# carcomputer_split1_top.net
KiCad netlist of a schematic drawn in EAGLE
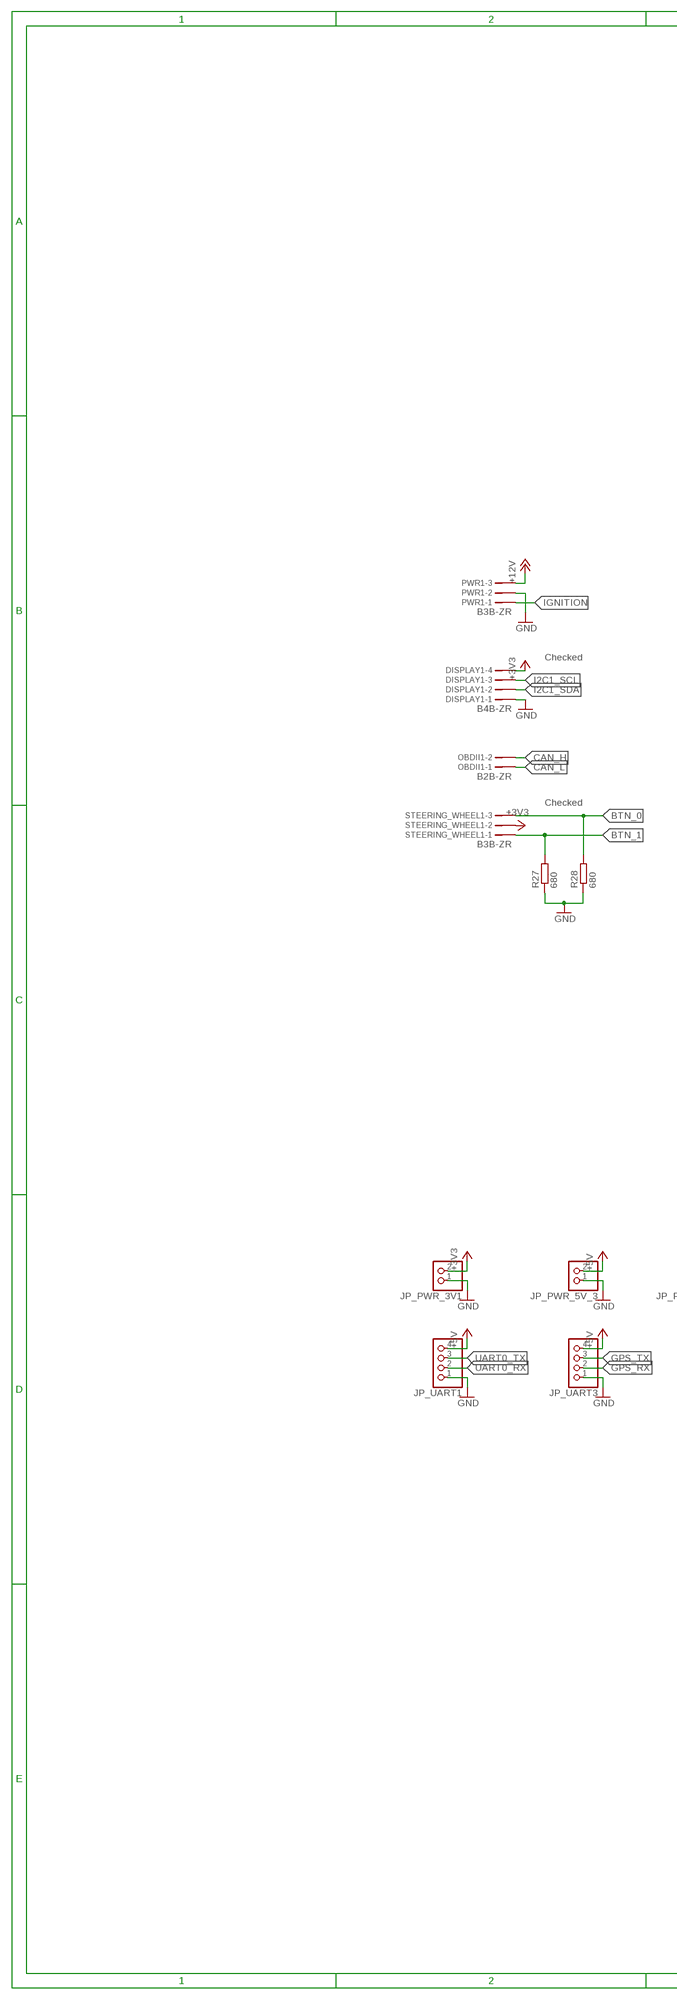
[diagram p0: schematic, sheet 1, part 1 of 2]
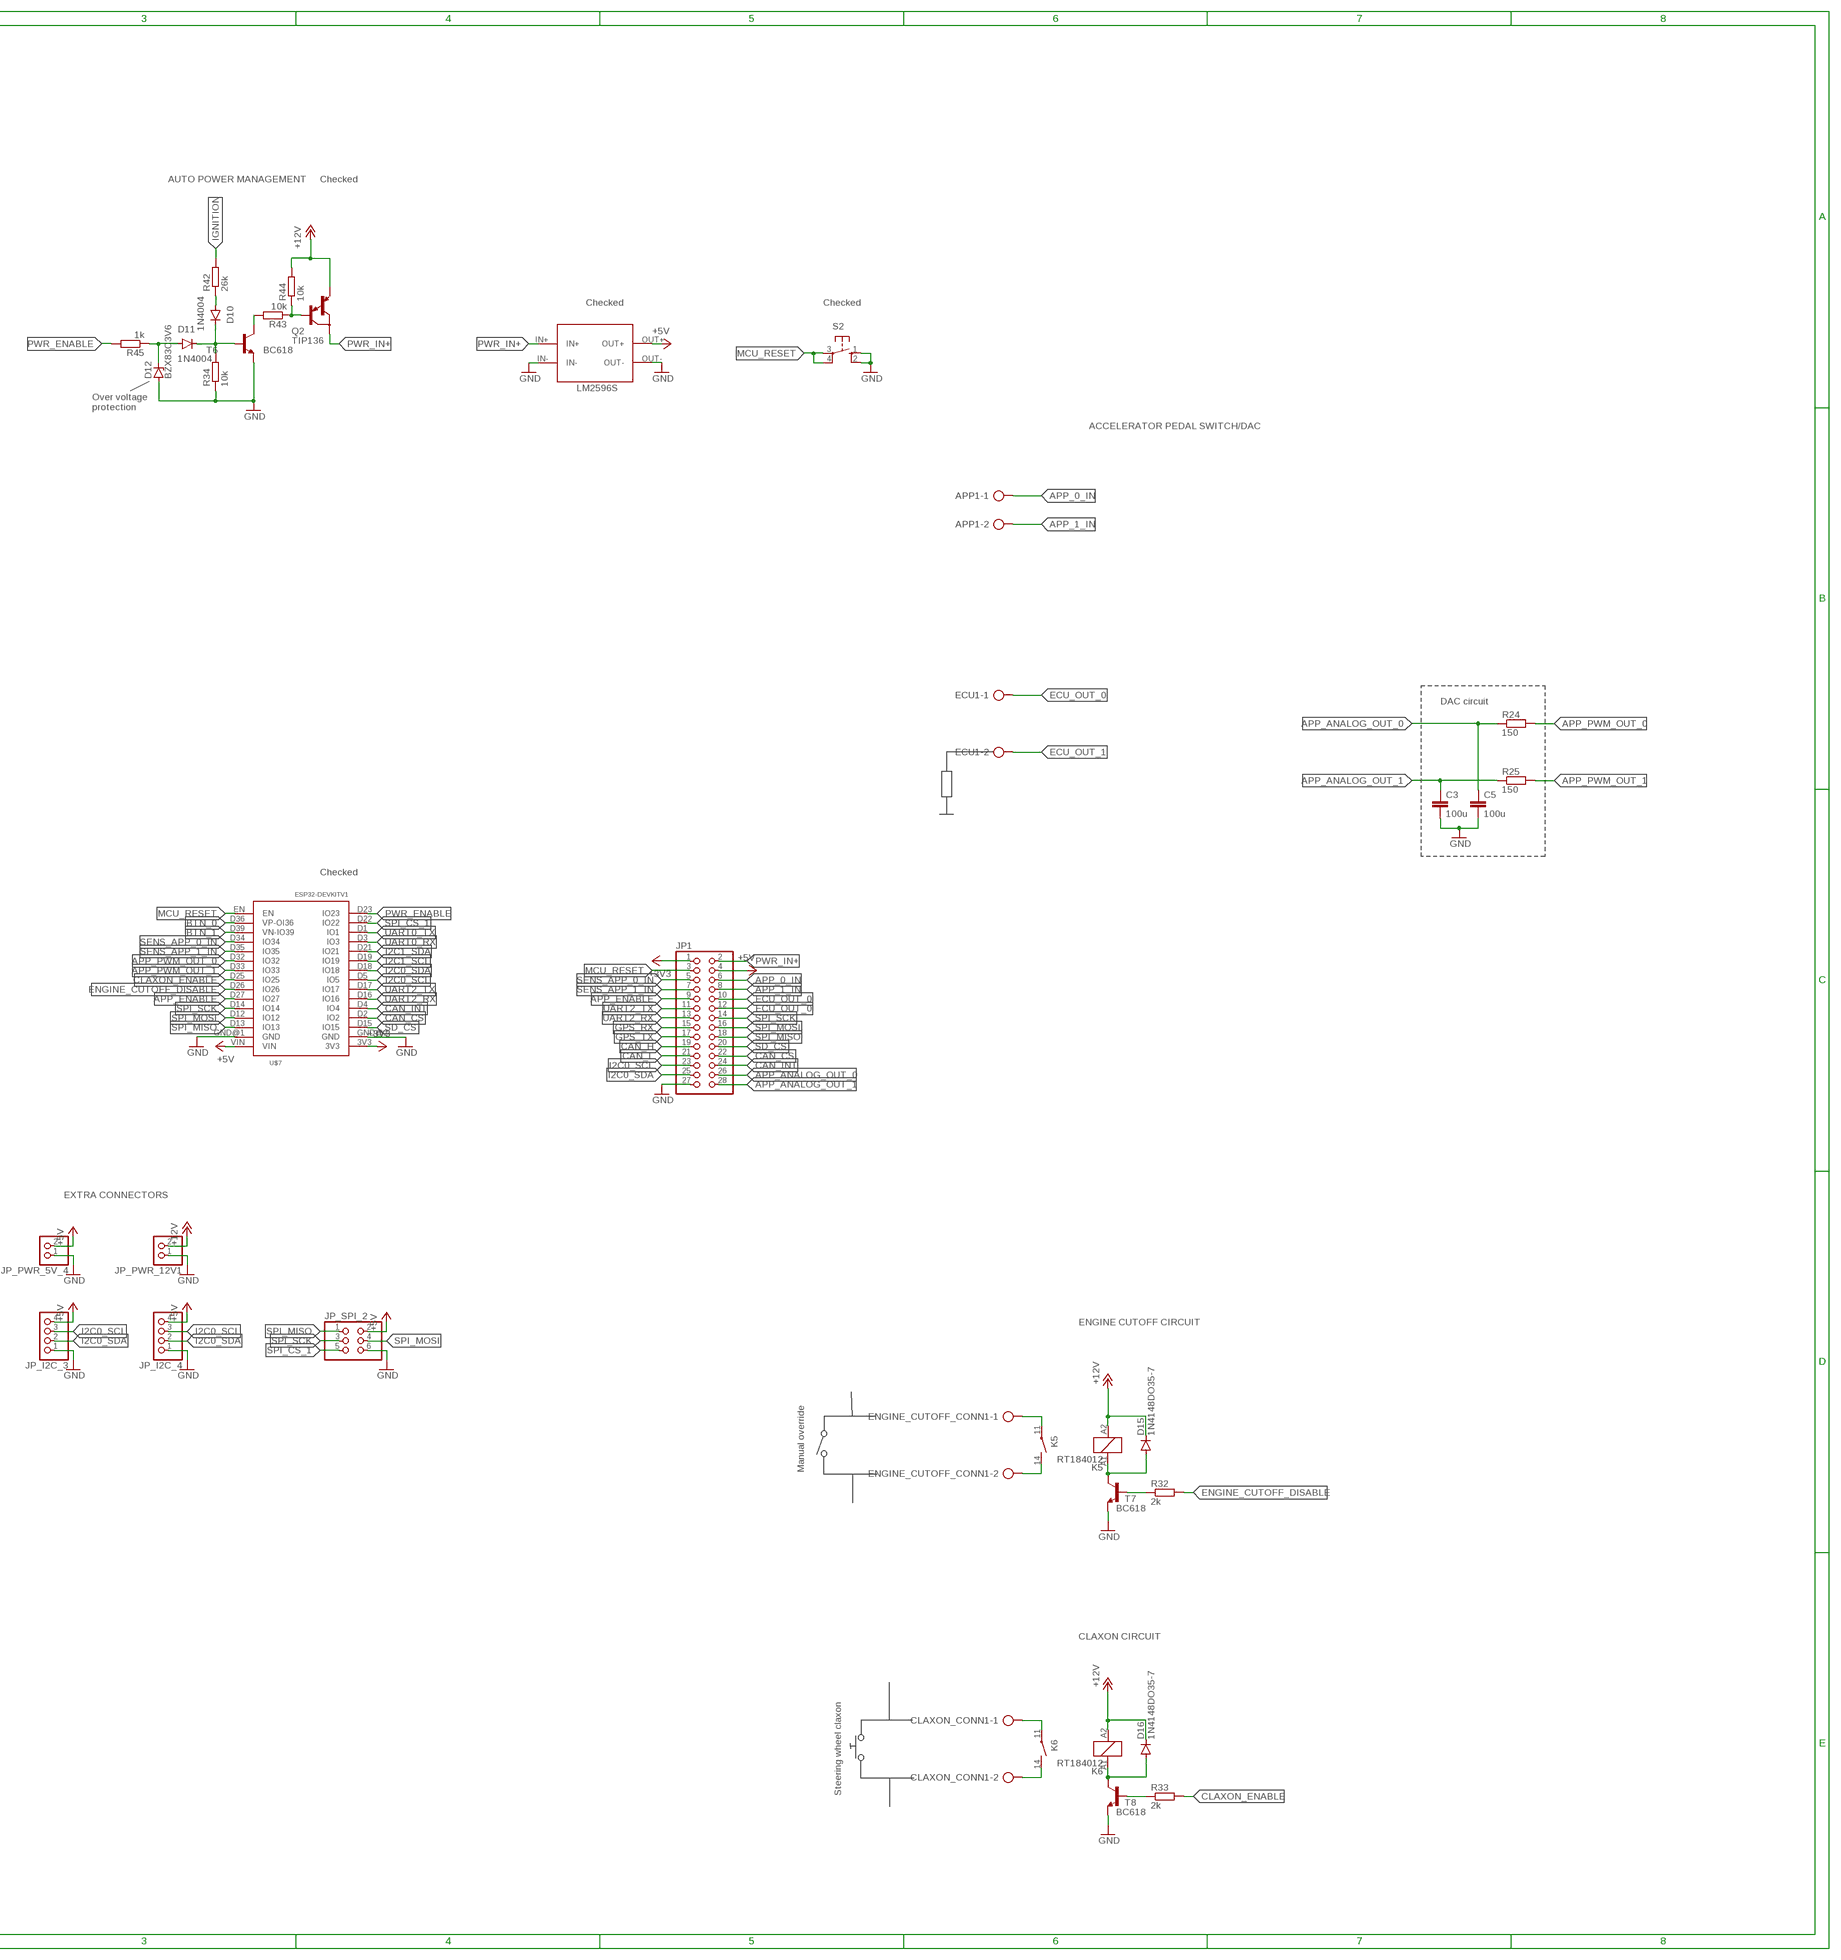
[diagram p1: schematic, sheet 1, part 2 of 2]

(export (version "E")
  (design (tool "Eeschema 10.0.6"))
  (components
    (comp (ref "APP1")
      (value "AK300/2")
      (footprint "eagle-import:AK300_2")
      (libsource (lib "eagle-import") (part "AK300/2"))
    )
    (comp (ref "C3")
      (value "100u")
      (footprint "eagle-import:C025-050X050")
      (libsource (lib "eagle-import") (part "C-EU025-050X050"))
    )
    (comp (ref "C5")
      (value "100u")
      (footprint "eagle-import:C025-050X050")
      (libsource (lib "eagle-import") (part "C-EU025-050X050"))
    )
    (comp (ref "CLAXON_CONN1")
      (value "AK300/2")
      (footprint "eagle-import:AK300_2")
      (libsource (lib "eagle-import") (part "AK300/2"))
    )
    (comp (ref "D10")
      (value "1N4004")
      (footprint "eagle-import:DO41-10")
      (libsource (lib "eagle-import") (part "1N4004"))
    )
    (comp (ref "D11")
      (value "1N4004")
      (footprint "eagle-import:DO41-10")
      (libsource (lib "eagle-import") (part "1N4004"))
    )
    (comp (ref "D12")
      (value "BZX83C3V6")
      (footprint "eagle-import:DO41Z10")
      (libsource (lib "eagle-import") (part "BZX85"))
    )
    (comp (ref "D15")
      (value "1N4148DO35-7")
      (footprint "eagle-import:DO35-7")
      (libsource (lib "eagle-import") (part "1N4148DO35-7"))
    )
    (comp (ref "D16")
      (value "1N4148DO35-7")
      (footprint "eagle-import:DO35-7")
      (libsource (lib "eagle-import") (part "1N4148DO35-7"))
    )
    (comp (ref "DISPLAY1")
      (value "B4B-ZR")
      (footprint "eagle-import:B4B-ZR")
      (fields (field (name "MF") "FARNELL") (field (name "MPN") "B4B-ZR(LF)(SN)"))
      (libsource (lib "eagle-import") (part "?4B-ZRB"))
    )
    (comp (ref "ECU1")
      (value "AK300/2")
      (footprint "eagle-import:AK300_2")
      (libsource (lib "eagle-import") (part "AK300/2"))
    )
    (comp (ref "ENGINE_CUTOFF_CONN1")
      (value "AK300/2")
      (footprint "eagle-import:AK300_2")
      (libsource (lib "eagle-import") (part "AK300/2"))
    )
    (comp (ref "JP1")
      (value "PINHD-2X14")
      (footprint "eagle-import:2X14")
      (libsource (lib "eagle-import") (part "PINHD-2X14"))
    )
    (comp (ref "JP_I2C_3")
      (value "PINHD-1X4")
      (footprint "eagle-import:1X04")
      (libsource (lib "eagle-import") (part "PINHD-1X4"))
    )
    (comp (ref "JP_I2C_4")
      (value "PINHD-1X4")
      (footprint "eagle-import:1X04")
      (libsource (lib "eagle-import") (part "PINHD-1X4"))
    )
    (comp (ref "JP_PWR_3V1")
      (value "PINHD-1X2")
      (footprint "eagle-import:1X02")
      (libsource (lib "eagle-import") (part "PINHD-1X2"))
    )
    (comp (ref "JP_PWR_5V_3")
      (value "PINHD-1X2")
      (footprint "eagle-import:1X02")
      (libsource (lib "eagle-import") (part "PINHD-1X2"))
    )
    (comp (ref "JP_PWR_5V_4")
      (value "PINHD-1X2")
      (footprint "eagle-import:1X02")
      (libsource (lib "eagle-import") (part "PINHD-1X2"))
    )
    (comp (ref "JP_PWR_12V1")
      (value "PINHD-1X2")
      (footprint "eagle-import:1X02")
      (libsource (lib "eagle-import") (part "PINHD-1X2"))
    )
    (comp (ref "JP_SPI_2")
      (value "PINHD-2X3")
      (footprint "eagle-import:2X03")
      (libsource (lib "eagle-import") (part "PINHD-2X3"))
    )
    (comp (ref "JP_UART1")
      (value "PINHD-1X4")
      (footprint "eagle-import:1X04")
      (libsource (lib "eagle-import") (part "PINHD-1X4"))
    )
    (comp (ref "JP_UART3")
      (value "PINHD-1X4")
      (footprint "eagle-import:1X04")
      (libsource (lib "eagle-import") (part "PINHD-1X4"))
    )
    (comp (ref "K5")
      (value "RT184012")
      (footprint "eagle-import:RT-N_O12A3.5")
      (fields (field (name "MF") "TYCO ELECTRONICS"))
      (libsource (lib "eagle-import") (part "RT?184012"))
    )
    (comp (ref "K6")
      (value "RT184012")
      (footprint "eagle-import:RT-N_O12A3.5")
      (fields (field (name "MF") "TYCO ELECTRONICS"))
      (libsource (lib "eagle-import") (part "RT?184012"))
    )
    (comp (ref "OBDII1")
      (value "B2B-ZR")
      (footprint "eagle-import:B2B-ZR")
      (libsource (lib "eagle-import") (part "?2B-ZRB"))
    )
    (comp (ref "PWR1")
      (value "B3B-ZR")
      (footprint "eagle-import:B3B-ZR")
      (libsource (lib "eagle-import") (part "?3B-ZRB"))
    )
    (comp (ref "Q2")
      (value "TIP136")
      (footprint "eagle-import:TO220")
      (libsource (lib "eagle-import") (part "TIP136"))
    )
    (comp (ref "R24")
      (value "150")
      (footprint "eagle-import:0207_7")
      (libsource (lib "eagle-import") (part "R-EU_0207/7"))
    )
    (comp (ref "R25")
      (value "150")
      (footprint "eagle-import:0207_7")
      (libsource (lib "eagle-import") (part "R-EU_0207/7"))
    )
    (comp (ref "R27")
      (value "680")
      (footprint "eagle-import:0207_7")
      (libsource (lib "eagle-import") (part "R-EU_0207/7"))
    )
    (comp (ref "R28")
      (value "680")
      (footprint "eagle-import:0207_7")
      (libsource (lib "eagle-import") (part "R-EU_0207/7"))
    )
    (comp (ref "R32")
      (value "2k")
      (footprint "eagle-import:0207_7")
      (libsource (lib "eagle-import") (part "R-EU_0207/7"))
    )
    (comp (ref "R33")
      (value "2k")
      (footprint "eagle-import:0207_7")
      (libsource (lib "eagle-import") (part "R-EU_0207/7"))
    )
    (comp (ref "R34")
      (value "10k")
      (footprint "eagle-import:0207_7")
      (libsource (lib "eagle-import") (part "R-EU_0207/7"))
    )
    (comp (ref "R42")
      (value "26k")
      (footprint "eagle-import:0207_7")
      (libsource (lib "eagle-import") (part "R-EU_0207/7"))
    )
    (comp (ref "R43")
      (value "10k")
      (footprint "eagle-import:0207_7")
      (libsource (lib "eagle-import") (part "R-EU_0207/7"))
    )
    (comp (ref "R44")
      (value "10k")
      (footprint "eagle-import:0207_7")
      (libsource (lib "eagle-import") (part "R-EU_0207/7"))
    )
    (comp (ref "R45")
      (value "1k")
      (footprint "eagle-import:0207_7")
      (libsource (lib "eagle-import") (part "R-EU_0207/7"))
    )
    (comp (ref "S2")
      (value "10-XX")
      (footprint "eagle-import:B3F-10XX")
      (fields (field (name "MPN") "B3F-1000"))
      (libsource (lib "eagle-import") (part "10-XX"))
    )
    (comp (ref "STEERING_WHEEL1")
      (value "B3B-ZR")
      (footprint "eagle-import:B3B-ZR")
      (libsource (lib "eagle-import") (part "?3B-ZRB"))
    )
    (comp (ref "T6")
      (value "BC618")
      (footprint "eagle-import:TO92-EBC")
      (libsource (lib "eagle-import") (part "BC618"))
    )
    (comp (ref "T7")
      (value "BC618")
      (footprint "eagle-import:TO92-EBC")
      (libsource (lib "eagle-import") (part "BC618"))
    )
    (comp (ref "T8")
      (value "BC618")
      (footprint "eagle-import:TO92-EBC")
      (libsource (lib "eagle-import") (part "BC618"))
    )
    (comp (ref "U$7")
      (value "ESP32DEVKITV1")
      (footprint "eagle-import:ESP32-DEVKITV1")
      (libsource (lib "eagle-import") (part "ESP32DEVKITV1"))
    )
    (comp (ref "U$10")
      (value "LM2596S")
      (footprint "eagle-import:LM2596S")
      (libsource (lib "eagle-import") (part "LM2596S"))
    )
  )
  (nets
    (net (code "1") (name "+3V3") (class "Default")
      (node (ref "DISPLAY1") (pin "4") (pinfunction "1_4") (pintype "passive"))
      (node (ref "JP1") (pin "1") (pinfunction "1_1") (pintype "passive"))
      (node (ref "JP_PWR_3V1") (pin "2") (pinfunction "2_2") (pintype "passive"))
      (node (ref "STEERING_WHEEL1") (pin "2") (pinfunction "1_2") (pintype "passive"))
      (node (ref "U$7") (pin "3V3") (pinfunction "3V3_3V3") (pintype "bidirectional"))
    )
    (net (code "2") (name "+5V") (class "Default")
      (node (ref "JP1") (pin "4") (pinfunction "4_4") (pintype "passive"))
      (node (ref "JP_I2C_3") (pin "4") (pinfunction "4_4") (pintype "passive"))
      (node (ref "JP_I2C_4") (pin "4") (pinfunction "4_4") (pintype "passive"))
      (node (ref "JP_PWR_5V_3") (pin "2") (pinfunction "2_2") (pintype "passive"))
      (node (ref "JP_PWR_5V_4") (pin "2") (pinfunction "2_2") (pintype "passive"))
      (node (ref "JP_SPI_2") (pin "2") (pinfunction "2_2") (pintype "passive"))
      (node (ref "JP_UART1") (pin "4") (pinfunction "4_4") (pintype "passive"))
      (node (ref "JP_UART3") (pin "4") (pinfunction "4_4") (pintype "passive"))
      (node (ref "U$10") (pin "OUT+") (pinfunction "OUT+_OUT+") (pintype "bidirectional"))
      (node (ref "U$7") (pin "VIN") (pinfunction "VIN_VIN") (pintype "bidirectional"))
    )
    (net (code "3") (name "+12V") (class "Default")
      (node (ref "D15") (pin "C") (pinfunction "C_C") (pintype "passive"))
      (node (ref "D16") (pin "C") (pinfunction "C_C") (pintype "passive"))
      (node (ref "JP_PWR_12V1") (pin "2") (pinfunction "2_2") (pintype "passive"))
      (node (ref "K5") (pin "A2") (pinfunction "2_A2") (pintype "passive"))
      (node (ref "K6") (pin "A2") (pinfunction "2_A2") (pintype "passive"))
      (node (ref "PWR1") (pin "3") (pinfunction "1_3") (pintype "passive"))
      (node (ref "Q2") (pin "3") (pinfunction "E_3") (pintype "passive"))
      (node (ref "R44") (pin "2") (pinfunction "2_2") (pintype "passive"))
    )
    (net (code "4") (name "APP_0_IN") (class "Default")
      (node (ref "APP1") (pin "1") (pinfunction "KL_1") (pintype "passive"))
      (node (ref "JP1") (pin "6") (pinfunction "6_6") (pintype "passive"))
    )
    (net (code "5") (name "APP_1_IN") (class "Default")
      (node (ref "APP1") (pin "2") (pinfunction "KL_2") (pintype "passive"))
      (node (ref "JP1") (pin "8") (pinfunction "8_8") (pintype "passive"))
    )
    (net (code "6") (name "APP_ANALOG_OUT_0") (class "Default")
      (node (ref "C5") (pin "1") (pinfunction "1_1") (pintype "passive"))
      (node (ref "JP1") (pin "26") (pinfunction "26_26") (pintype "passive"))
      (node (ref "R24") (pin "1") (pinfunction "1_1") (pintype "passive"))
    )
    (net (code "7") (name "APP_ANALOG_OUT_1") (class "Default")
      (node (ref "C3") (pin "1") (pinfunction "1_1") (pintype "passive"))
      (node (ref "JP1") (pin "28") (pinfunction "28_28") (pintype "passive"))
      (node (ref "R25") (pin "1") (pinfunction "1_1") (pintype "passive"))
    )
    (net (code "8") (name "APP_ENABLE") (class "Default")
      (node (ref "JP1") (pin "9") (pinfunction "9_9") (pintype "passive"))
      (node (ref "U$7") (pin "D27") (pinfunction "IO27_D27") (pintype "bidirectional"))
    )
    (net (code "9") (name "APP_PWM_OUT_0") (class "Default")
      (node (ref "R24") (pin "2") (pinfunction "2_2") (pintype "passive"))
      (node (ref "U$7") (pin "D32") (pinfunction "IO32_D32") (pintype "bidirectional"))
    )
    (net (code "10") (name "APP_PWM_OUT_1") (class "Default")
      (node (ref "R25") (pin "2") (pinfunction "2_2") (pintype "passive"))
      (node (ref "U$7") (pin "D33") (pinfunction "IO33_D33") (pintype "bidirectional"))
    )
    (net (code "11") (name "BTN_0") (class "Default")
      (node (ref "R28") (pin "2") (pinfunction "2_2") (pintype "passive"))
      (node (ref "STEERING_WHEEL1") (pin "3") (pinfunction "1_3") (pintype "passive"))
      (node (ref "U$7") (pin "D36") (pinfunction "VP-OI36_D36") (pintype "bidirectional"))
    )
    (net (code "12") (name "BTN_1") (class "Default")
      (node (ref "R27") (pin "2") (pinfunction "2_2") (pintype "passive"))
      (node (ref "STEERING_WHEEL1") (pin "1") (pinfunction "1_1") (pintype "passive"))
      (node (ref "U$7") (pin "D39") (pinfunction "VN-IO39_D39") (pintype "bidirectional"))
    )
    (net (code "13") (name "CAN_CS") (class "Default")
      (node (ref "JP1") (pin "22") (pinfunction "22_22") (pintype "passive"))
      (node (ref "U$7") (pin "D2") (pinfunction "IO2_D2") (pintype "bidirectional"))
    )
    (net (code "14") (name "CAN_H") (class "Default")
      (node (ref "JP1") (pin "19") (pinfunction "19_19") (pintype "passive"))
      (node (ref "OBDII1") (pin "2") (pinfunction "1_2") (pintype "passive"))
    )
    (net (code "15") (name "CAN_INT") (class "Default")
      (node (ref "JP1") (pin "24") (pinfunction "24_24") (pintype "passive"))
      (node (ref "U$7") (pin "D4") (pinfunction "IO4_D4") (pintype "bidirectional"))
    )
    (net (code "16") (name "CAN_L") (class "Default")
      (node (ref "JP1") (pin "21") (pinfunction "21_21") (pintype "passive"))
      (node (ref "OBDII1") (pin "1") (pinfunction "1_1") (pintype "passive"))
    )
    (net (code "17") (name "CLAXON_ENABLE") (class "Default")
      (node (ref "R33") (pin "2") (pinfunction "2_2") (pintype "passive"))
      (node (ref "U$7") (pin "D25") (pinfunction "IO25_D25") (pintype "bidirectional"))
    )
    (net (code "18") (name "ECU_OUT_0") (class "Default")
      (node (ref "ECU1") (pin "1") (pinfunction "KL_1") (pintype "passive"))
      (node (ref "JP1") (pin "10") (pinfunction "10_10") (pintype "passive"))
      (node (ref "JP1") (pin "12") (pinfunction "12_12") (pintype "passive"))
    )
    (net (code "19") (name "ECU_OUT_1") (class "Default")
      (node (ref "ECU1") (pin "2") (pinfunction "KL_2") (pintype "passive"))
    )
    (net (code "20") (name "ENGINE_CUTOFF_DISABLE") (class "Default")
      (node (ref "R32") (pin "2") (pinfunction "2_2") (pintype "passive"))
      (node (ref "U$7") (pin "D26") (pinfunction "IO26_D26") (pintype "bidirectional"))
    )
    (net (code "21") (name "GND") (class "Default")
      (node (ref "C3") (pin "2") (pinfunction "2_2") (pintype "passive"))
      (node (ref "C5") (pin "2") (pinfunction "2_2") (pintype "passive"))
      (node (ref "D12") (pin "A") (pinfunction "A_A") (pintype "passive"))
      (node (ref "DISPLAY1") (pin "1") (pinfunction "1_1") (pintype "passive"))
      (node (ref "JP1") (pin "27") (pinfunction "27_27") (pintype "passive"))
      (node (ref "JP_I2C_3") (pin "1") (pinfunction "1_1") (pintype "passive"))
      (node (ref "JP_I2C_4") (pin "1") (pinfunction "1_1") (pintype "passive"))
      (node (ref "JP_PWR_12V1") (pin "1") (pinfunction "1_1") (pintype "passive"))
      (node (ref "JP_PWR_3V1") (pin "1") (pinfunction "1_1") (pintype "passive"))
      (node (ref "JP_PWR_5V_3") (pin "1") (pinfunction "1_1") (pintype "passive"))
      (node (ref "JP_PWR_5V_4") (pin "1") (pinfunction "1_1") (pintype "passive"))
      (node (ref "JP_SPI_2") (pin "6") (pinfunction "6_6") (pintype "passive"))
      (node (ref "JP_UART1") (pin "1") (pinfunction "1_1") (pintype "passive"))
      (node (ref "JP_UART3") (pin "1") (pinfunction "1_1") (pintype "passive"))
      (node (ref "PWR1") (pin "2") (pinfunction "1_2") (pintype "passive"))
      (node (ref "R27") (pin "1") (pinfunction "1_1") (pintype "passive"))
      (node (ref "R28") (pin "1") (pinfunction "1_1") (pintype "passive"))
      (node (ref "R34") (pin "1") (pinfunction "1_1") (pintype "passive"))
      (node (ref "S2") (pin "1") (pinfunction "S_1") (pintype "passive"))
      (node (ref "S2") (pin "2") (pinfunction "S1_2") (pintype "passive"))
      (node (ref "T6") (pin "E") (pinfunction "E_E") (pintype "passive"))
      (node (ref "T7") (pin "E") (pinfunction "E_E") (pintype "passive"))
      (node (ref "T8") (pin "E") (pinfunction "E_E") (pintype "passive"))
      (node (ref "U$10") (pin "IN-") (pinfunction "IN-_IN-") (pintype "bidirectional"))
      (node (ref "U$10") (pin "OUT-") (pinfunction "OUT-_OUT-") (pintype "bidirectional"))
      (node (ref "U$7") (pin "GND@1") (pinfunction "GND_GND@1") (pintype "bidirectional"))
      (node (ref "U$7") (pin "GND@2") (pinfunction "GND_GND@2") (pintype "bidirectional"))
    )
    (net (code "22") (name "GPS_RX") (class "Default")
      (node (ref "JP1") (pin "15") (pinfunction "15_15") (pintype "passive"))
      (node (ref "JP_UART3") (pin "2") (pinfunction "2_2") (pintype "passive"))
    )
    (net (code "23") (name "GPS_TX") (class "Default")
      (node (ref "JP1") (pin "17") (pinfunction "17_17") (pintype "passive"))
      (node (ref "JP_UART3") (pin "3") (pinfunction "3_3") (pintype "passive"))
    )
    (net (code "24") (name "I2C0_SCL") (class "Default")
      (node (ref "JP1") (pin "23") (pinfunction "23_23") (pintype "passive"))
      (node (ref "JP_I2C_3") (pin "3") (pinfunction "3_3") (pintype "passive"))
      (node (ref "JP_I2C_4") (pin "3") (pinfunction "3_3") (pintype "passive"))
      (node (ref "U$7") (pin "D5") (pinfunction "IO5_D5") (pintype "bidirectional"))
    )
    (net (code "25") (name "I2C0_SDA") (class "Default")
      (node (ref "JP1") (pin "25") (pinfunction "25_25") (pintype "passive"))
      (node (ref "JP_I2C_3") (pin "2") (pinfunction "2_2") (pintype "passive"))
      (node (ref "JP_I2C_4") (pin "2") (pinfunction "2_2") (pintype "passive"))
      (node (ref "U$7") (pin "D18") (pinfunction "IO18_D18") (pintype "bidirectional"))
    )
    (net (code "26") (name "I2C1_SCL") (class "Default")
      (node (ref "DISPLAY1") (pin "3") (pinfunction "1_3") (pintype "passive"))
      (node (ref "U$7") (pin "D19") (pinfunction "IO19_D19") (pintype "bidirectional"))
    )
    (net (code "27") (name "I2C1_SDA") (class "Default")
      (node (ref "DISPLAY1") (pin "2") (pinfunction "1_2") (pintype "passive"))
      (node (ref "U$7") (pin "D21") (pinfunction "IO21_D21") (pintype "bidirectional"))
    )
    (net (code "28") (name "IGNITION") (class "Default")
      (node (ref "PWR1") (pin "1") (pinfunction "1_1") (pintype "passive"))
      (node (ref "R42") (pin "2") (pinfunction "2_2") (pintype "passive"))
    )
    (net (code "29") (name "MCU_RESET") (class "Default")
      (node (ref "JP1") (pin "3") (pinfunction "3_3") (pintype "passive"))
      (node (ref "S2") (pin "3") (pinfunction "P_3") (pintype "passive"))
      (node (ref "S2") (pin "4") (pinfunction "P1_4") (pintype "passive"))
      (node (ref "U$7") (pin "EN") (pinfunction "EN_EN") (pintype "bidirectional"))
    )
    (net (code "30") (name "Net-(CLAXON_CONN1A-KL)") (class "Default")
      (node (ref "CLAXON_CONN1") (pin "1") (pinfunction "KL_1") (pintype "passive"))
      (node (ref "K6") (pin "11") (pinfunction "P_11") (pintype "passive"))
    )
    (net (code "31") (name "Net-(CLAXON_CONN1B-KL)") (class "Default")
      (node (ref "CLAXON_CONN1") (pin "2") (pinfunction "KL_2") (pintype "passive"))
      (node (ref "K6") (pin "14") (pinfunction "S_14") (pintype "passive"))
    )
    (net (code "32") (name "Net-(D10-PadA)") (class "Default")
      (node (ref "D10") (pin "A") (pinfunction "A_A") (pintype "passive"))
      (node (ref "R42") (pin "1") (pinfunction "1_1") (pintype "passive"))
    )
    (net (code "33") (name "Net-(D10-PadC)") (class "Default")
      (node (ref "D10") (pin "C") (pinfunction "C_C") (pintype "passive"))
      (node (ref "D11") (pin "C") (pinfunction "C_C") (pintype "passive"))
      (node (ref "R34") (pin "2") (pinfunction "2_2") (pintype "passive"))
      (node (ref "T6") (pin "B") (pinfunction "B_B") (pintype "passive"))
    )
    (net (code "34") (name "Net-(D11-PadA)") (class "Default")
      (node (ref "D11") (pin "A") (pinfunction "A_A") (pintype "passive"))
      (node (ref "D12") (pin "C") (pinfunction "C_C") (pintype "passive"))
      (node (ref "R45") (pin "1") (pinfunction "1_1") (pintype "passive"))
    )
    (net (code "35") (name "Net-(ENGINE_CUTOFF_CONN1A-KL)") (class "Default")
      (node (ref "ENGINE_CUTOFF_CONN1") (pin "1") (pinfunction "KL_1") (pintype "passive"))
      (node (ref "K5") (pin "11") (pinfunction "P_11") (pintype "passive"))
    )
    (net (code "36") (name "Net-(ENGINE_CUTOFF_CONN1B-KL)") (class "Default")
      (node (ref "ENGINE_CUTOFF_CONN1") (pin "2") (pinfunction "KL_2") (pintype "passive"))
      (node (ref "K5") (pin "14") (pinfunction "S_14") (pintype "passive"))
    )
    (net (code "37") (name "Net-(K5A-1)") (class "Default")
      (node (ref "D15") (pin "A") (pinfunction "A_A") (pintype "passive"))
      (node (ref "K5") (pin "A1") (pinfunction "1_A1") (pintype "passive"))
      (node (ref "T7") (pin "C") (pinfunction "C_C") (pintype "passive"))
    )
    (net (code "38") (name "Net-(K6A-1)") (class "Default")
      (node (ref "D16") (pin "A") (pinfunction "A_A") (pintype "passive"))
      (node (ref "K6") (pin "A1") (pinfunction "1_A1") (pintype "passive"))
      (node (ref "T8") (pin "C") (pinfunction "C_C") (pintype "passive"))
    )
    (net (code "39") (name "Net-(Q2-B)") (class "Default")
      (node (ref "Q2") (pin "1") (pinfunction "B_1") (pintype "passive"))
      (node (ref "R43") (pin "1") (pinfunction "1_1") (pintype "passive"))
      (node (ref "R44") (pin "1") (pinfunction "1_1") (pintype "passive"))
    )
    (net (code "40") (name "Net-(R32-Pad1)") (class "Default")
      (node (ref "R32") (pin "1") (pinfunction "1_1") (pintype "passive"))
      (node (ref "T7") (pin "B") (pinfunction "B_B") (pintype "passive"))
    )
    (net (code "41") (name "Net-(R33-Pad1)") (class "Default")
      (node (ref "R33") (pin "1") (pinfunction "1_1") (pintype "passive"))
      (node (ref "T8") (pin "B") (pinfunction "B_B") (pintype "passive"))
    )
    (net (code "42") (name "Net-(R43-Pad2)") (class "Default")
      (node (ref "R43") (pin "2") (pinfunction "2_2") (pintype "passive"))
      (node (ref "T6") (pin "C") (pinfunction "C_C") (pintype "passive"))
    )
    (net (code "43") (name "PWR_ENABLE") (class "Default")
      (node (ref "R45") (pin "2") (pinfunction "2_2") (pintype "passive"))
      (node (ref "U$7") (pin "D23") (pinfunction "IO23_D23") (pintype "bidirectional"))
    )
    (net (code "44") (name "PWR_IN+") (class "Default")
      (node (ref "JP1") (pin "2") (pinfunction "2_2") (pintype "passive"))
      (node (ref "Q2") (pin "2") (pinfunction "C_2") (pintype "passive"))
      (node (ref "U$10") (pin "IN+") (pinfunction "IN+_IN+") (pintype "bidirectional"))
    )
    (net (code "45") (name "SD_CS") (class "Default")
      (node (ref "JP1") (pin "20") (pinfunction "20_20") (pintype "passive"))
      (node (ref "U$7") (pin "D15") (pinfunction "IO15_D15") (pintype "bidirectional"))
    )
    (net (code "46") (name "SENS_APP_0_IN") (class "Default")
      (node (ref "JP1") (pin "5") (pinfunction "5_5") (pintype "passive"))
      (node (ref "U$7") (pin "D34") (pinfunction "IO34_D34") (pintype "bidirectional"))
    )
    (net (code "47") (name "SENS_APP_1_IN") (class "Default")
      (node (ref "JP1") (pin "7") (pinfunction "7_7") (pintype "passive"))
      (node (ref "U$7") (pin "D35") (pinfunction "IO35_D35") (pintype "bidirectional"))
    )
    (net (code "48") (name "SPI_CS_1") (class "Default")
      (node (ref "JP_SPI_2") (pin "5") (pinfunction "5_5") (pintype "passive"))
      (node (ref "U$7") (pin "D22") (pinfunction "IO22_D22") (pintype "bidirectional"))
    )
    (net (code "49") (name "SPI_MISO") (class "Default")
      (node (ref "JP1") (pin "18") (pinfunction "18_18") (pintype "passive"))
      (node (ref "JP_SPI_2") (pin "1") (pinfunction "1_1") (pintype "passive"))
      (node (ref "U$7") (pin "D13") (pinfunction "IO13_D13") (pintype "bidirectional"))
    )
    (net (code "50") (name "SPI_MOSI") (class "Default")
      (node (ref "JP1") (pin "16") (pinfunction "16_16") (pintype "passive"))
      (node (ref "JP_SPI_2") (pin "4") (pinfunction "4_4") (pintype "passive"))
      (node (ref "U$7") (pin "D12") (pinfunction "IO12_D12") (pintype "bidirectional"))
    )
    (net (code "51") (name "SPI_SCK") (class "Default")
      (node (ref "JP1") (pin "14") (pinfunction "14_14") (pintype "passive"))
      (node (ref "JP_SPI_2") (pin "3") (pinfunction "3_3") (pintype "passive"))
      (node (ref "U$7") (pin "D14") (pinfunction "IO14_D14") (pintype "bidirectional"))
    )
    (net (code "52") (name "UART0_RX") (class "Default")
      (node (ref "JP_UART1") (pin "2") (pinfunction "2_2") (pintype "passive"))
      (node (ref "U$7") (pin "D3") (pinfunction "IO3_D3") (pintype "bidirectional"))
    )
    (net (code "53") (name "UART0_TX") (class "Default")
      (node (ref "JP_UART1") (pin "3") (pinfunction "3_3") (pintype "passive"))
      (node (ref "U$7") (pin "D1") (pinfunction "IO1_D1") (pintype "bidirectional"))
    )
    (net (code "54") (name "UART2_RX") (class "Default")
      (node (ref "JP1") (pin "13") (pinfunction "13_13") (pintype "passive"))
      (node (ref "U$7") (pin "D16") (pinfunction "IO16_D16") (pintype "bidirectional"))
    )
    (net (code "55") (name "UART2_TX") (class "Default")
      (node (ref "JP1") (pin "11") (pinfunction "11_11") (pintype "passive"))
      (node (ref "U$7") (pin "D17") (pinfunction "IO17_D17") (pintype "bidirectional"))
    )
  )
)
